# p2.net
KiCad netlist of a schematic drawn in Altium Designer
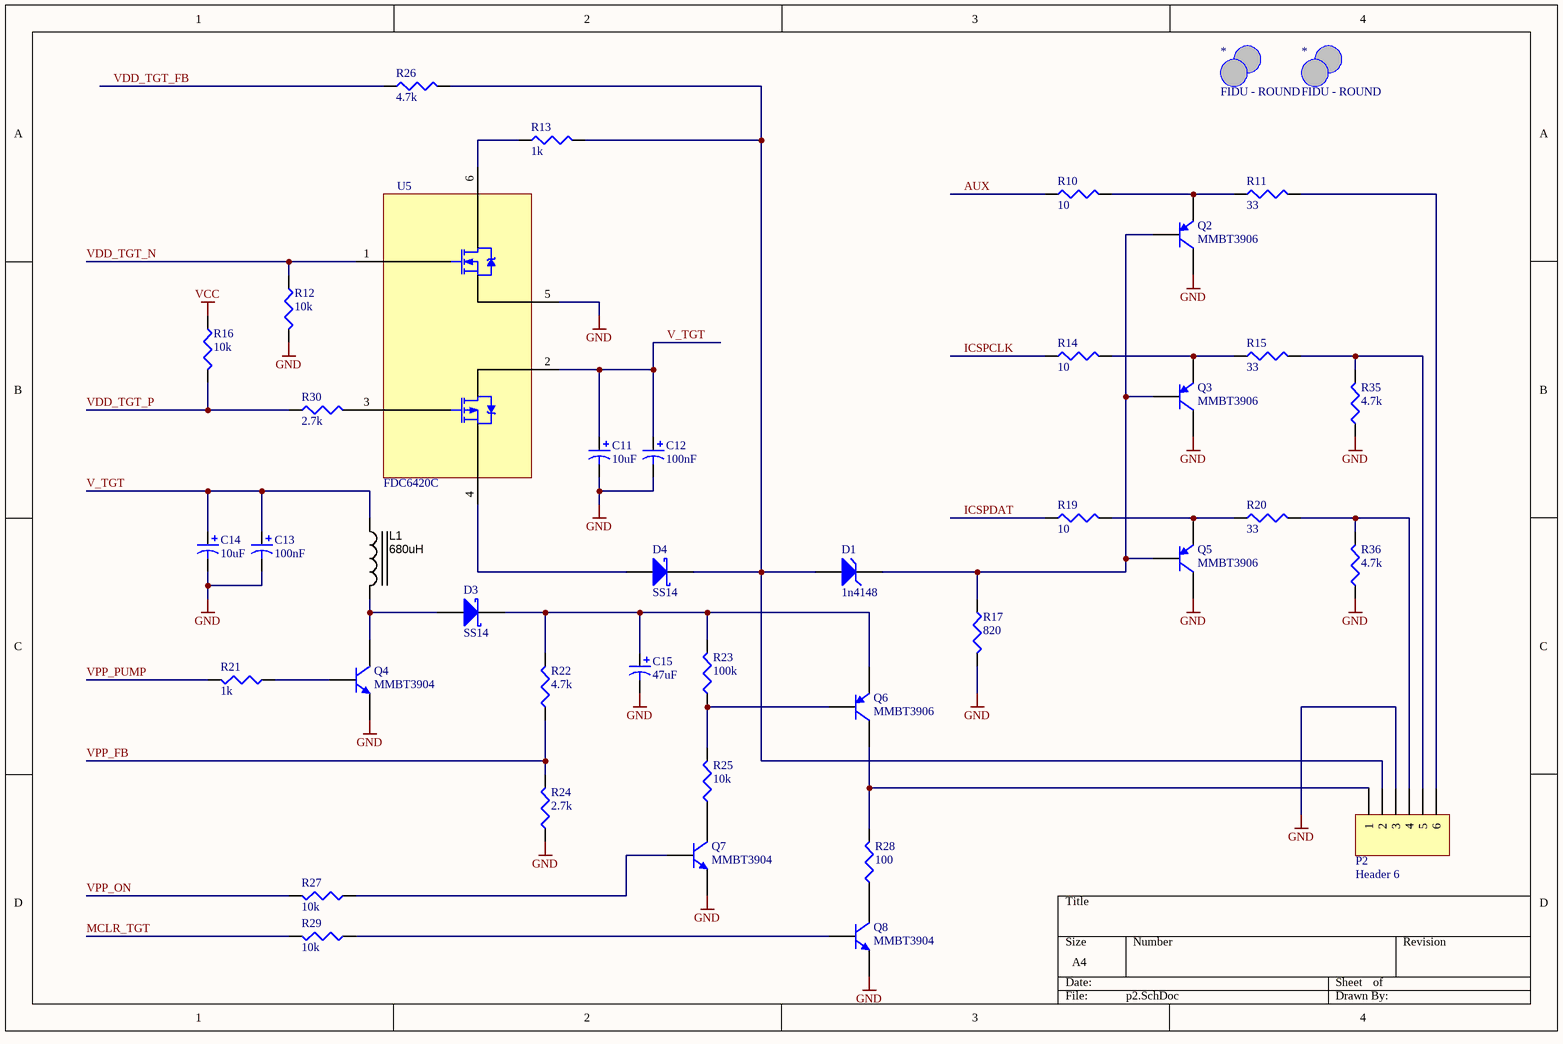
[diagram p0: p2.SchDoc]

(export (version "E")
  (design (tool "Eeschema 10.0.6"))
  (components
    (comp (ref "C11")
      (value "10uF")
      (footprint "C0805")
      (description "Polarized Capacitor (Surface Mount)")
      (fields (field (name "Comment") "Cap Pol3") (field (name "PUBLISHER") "Altium Limited"))
      (libsource (lib "Miscellaneous Devices") (part "Cap Pol3"))
    )
    (comp (ref "C12")
      (value "100nF")
      (footprint "C0805")
      (description "Polarized Capacitor (Surface Mount)")
      (fields (field (name "Comment") "Cap Pol3") (field (name "PUBLISHER") "Altium Limited"))
      (libsource (lib "Miscellaneous Devices") (part "Cap Pol3"))
    )
    (comp (ref "C13")
      (value "100nF")
      (footprint "C0805")
      (description "Polarized Capacitor (Surface Mount)")
      (fields (field (name "Comment") "Cap Pol3") (field (name "PUBLISHER") "Altium Limited"))
      (libsource (lib "Miscellaneous Devices") (part "Cap Pol3"))
    )
    (comp (ref "C14")
      (value "10uF")
      (footprint "C0805")
      (description "Polarized Capacitor (Surface Mount)")
      (fields (field (name "Comment") "Cap Pol3") (field (name "PUBLISHER") "Altium Limited"))
      (libsource (lib "Miscellaneous Devices") (part "Cap Pol3"))
    )
    (comp (ref "C15")
      (value "47uF")
      (footprint "C0805")
      (description "Polarized Capacitor (Surface Mount)")
      (fields (field (name "Comment") "Cap Pol3") (field (name "PUBLISHER") "Altium Limited"))
      (libsource (lib "Miscellaneous Devices") (part "Cap Pol3"))
    )
    (comp (ref "D1")
      (value "1n4148")
      (footprint "SOD-123")
      (description "Surface Mount Zener Diode")
      (fields (field (name "PUBLISHER") "Altium Limited"))
      (libsource (lib "Vishay Lite-On Discrete Diode") (part "BZT52C47"))
    )
    (comp (ref "D3")
      (value "SS14")
      (footprint "SMA")
      (description "Schottky Rectifier")
      (fields (field (name "PUBLISHER") "Altium Limited"))
      (libsource (lib "IR Rectifier - Schottky") (part "10MQ060N"))
    )
    (comp (ref "D4")
      (value "SS14")
      (footprint "SMA")
      (description "Schottky Rectifier")
      (fields (field (name "PUBLISHER") "Altium Limited"))
      (libsource (lib "IR Rectifier - Schottky") (part "10MQ060N"))
    )
    (comp (ref "L1")
      (value "680uH")
      (footprint "IND_WW_DR73")
      (description "Inductor Power 10µH 2.1A 7.6x7.6mm SMD")
      (fields (field (name "TOLERANCE") "±20%"))
      (libsource (lib "PBL - Inductors") (part "INDC_10u_DR73-100-R"))
    )
    (comp (ref "P2")
      (value "Header 6")
      (footprint "HDR1X6")
      (description "Header, 6-Pin")
      (fields (field (name "PUBLISHER") "Altium Limited"))
      (libsource (lib "Miscellaneous Connectors") (part "Header 6"))
    )
    (comp (ref "Q2")
      (value "MMBT3906")
      (footprint "SOT23_N")
      (description "PNP Switching Transistor")
      (fields (field (name "PUBLISHER") "Altium Limited"))
      (libsource (lib "Philips Discrete BJT - Low Power") (part "MMBT3906"))
    )
    (comp (ref "Q3")
      (value "MMBT3906")
      (footprint "SOT23_N")
      (description "PNP Switching Transistor")
      (fields (field (name "PUBLISHER") "Altium Limited"))
      (libsource (lib "Philips Discrete BJT - Low Power") (part "MMBT3906"))
    )
    (comp (ref "Q4")
      (value "MMBT3904")
      (footprint "SOT23_N")
      (description "NPN Switching Transistor")
      (fields (field (name "PUBLISHER") "Altium Limited"))
      (libsource (lib "Philips Discrete BJT - Low Power") (part "MMBT3904"))
    )
    (comp (ref "Q5")
      (value "MMBT3906")
      (footprint "SOT23_N")
      (description "PNP Switching Transistor")
      (fields (field (name "PUBLISHER") "Altium Limited"))
      (libsource (lib "Philips Discrete BJT - Low Power") (part "MMBT3906"))
    )
    (comp (ref "Q6")
      (value "MMBT3906")
      (footprint "SOT23_N")
      (description "PNP Switching Transistor")
      (fields (field (name "PUBLISHER") "Altium Limited"))
      (libsource (lib "Philips Discrete BJT - Low Power") (part "MMBT3906"))
    )
    (comp (ref "Q7")
      (value "MMBT3904")
      (footprint "SOT23_N")
      (description "NPN Switching Transistor")
      (fields (field (name "PUBLISHER") "Altium Limited"))
      (libsource (lib "Philips Discrete BJT - Low Power") (part "MMBT3904"))
    )
    (comp (ref "Q8")
      (value "MMBT3904")
      (footprint "SOT23_N")
      (description "NPN Switching Transistor")
      (fields (field (name "PUBLISHER") "Altium Limited"))
      (libsource (lib "Philips Discrete BJT - Low Power") (part "MMBT3904"))
    )
    (comp (ref "R10")
      (value "10")
      (footprint "RESC2012X70N")
      (description "Resistor")
      (fields (field (name "Comment") "Res3") (field (name "PUBLISHER") "Altium Limited"))
      (libsource (lib "Miscellaneous Devices") (part "Res3"))
    )
    (comp (ref "R11")
      (value "33")
      (footprint "RESC2012X70N")
      (description "Resistor")
      (fields (field (name "Comment") "Res3") (field (name "PUBLISHER") "Altium Limited"))
      (libsource (lib "Miscellaneous Devices") (part "Res3"))
    )
    (comp (ref "R12")
      (value "10k")
      (footprint "RESC2012X70N")
      (description "Resistor")
      (fields (field (name "Comment") "Res3") (field (name "PUBLISHER") "Altium Limited"))
      (libsource (lib "Miscellaneous Devices") (part "Res3"))
    )
    (comp (ref "R13")
      (value "1k")
      (footprint "RESC2012X70N")
      (description "Resistor")
      (fields (field (name "Comment") "Res3") (field (name "PUBLISHER") "Altium Limited"))
      (libsource (lib "Miscellaneous Devices") (part "Res3"))
    )
    (comp (ref "R14")
      (value "10")
      (footprint "RESC2012X70N")
      (description "Resistor")
      (fields (field (name "Comment") "Res3") (field (name "PUBLISHER") "Altium Limited"))
      (libsource (lib "Miscellaneous Devices") (part "Res3"))
    )
    (comp (ref "R15")
      (value "33")
      (footprint "RESC2012X70N")
      (description "Resistor")
      (fields (field (name "Comment") "Res3") (field (name "PUBLISHER") "Altium Limited"))
      (libsource (lib "Miscellaneous Devices") (part "Res3"))
    )
    (comp (ref "R16")
      (value "10k")
      (footprint "RESC2012X70N")
      (description "Resistor")
      (fields (field (name "Comment") "Res3") (field (name "PUBLISHER") "Altium Limited"))
      (libsource (lib "Miscellaneous Devices") (part "Res3"))
    )
    (comp (ref "R17")
      (value "820")
      (footprint "RESC2012X70N")
      (description "Resistor")
      (fields (field (name "Comment") "Res3") (field (name "PUBLISHER") "Altium Limited"))
      (libsource (lib "Miscellaneous Devices") (part "Res3"))
    )
    (comp (ref "R19")
      (value "10")
      (footprint "RESC2012X70N")
      (description "Resistor")
      (fields (field (name "Comment") "Res3") (field (name "PUBLISHER") "Altium Limited"))
      (libsource (lib "Miscellaneous Devices") (part "Res3"))
    )
    (comp (ref "R20")
      (value "33")
      (footprint "RESC2012X70N")
      (description "Resistor")
      (fields (field (name "Comment") "Res3") (field (name "PUBLISHER") "Altium Limited"))
      (libsource (lib "Miscellaneous Devices") (part "Res3"))
    )
    (comp (ref "R21")
      (value "1k")
      (footprint "RESC2012X70N")
      (description "Resistor")
      (fields (field (name "Comment") "Res3") (field (name "PUBLISHER") "Altium Limited"))
      (libsource (lib "Miscellaneous Devices") (part "Res3"))
    )
    (comp (ref "R22")
      (value "4.7k")
      (footprint "RESC2012X70N")
      (description "Resistor")
      (fields (field (name "Comment") "Res3") (field (name "PUBLISHER") "Altium Limited"))
      (libsource (lib "Miscellaneous Devices") (part "Res3"))
    )
    (comp (ref "R23")
      (value "100k")
      (footprint "RESC2012X70N")
      (description "Resistor")
      (fields (field (name "Comment") "Res3") (field (name "PUBLISHER") "Altium Limited"))
      (libsource (lib "Miscellaneous Devices") (part "Res3"))
    )
    (comp (ref "R24")
      (value "2.7k")
      (footprint "RESC2012X70N")
      (description "Resistor")
      (fields (field (name "Comment") "Res3") (field (name "PUBLISHER") "Altium Limited"))
      (libsource (lib "Miscellaneous Devices") (part "Res3"))
    )
    (comp (ref "R25")
      (value "10k")
      (footprint "RESC2012X70N")
      (description "Resistor")
      (fields (field (name "Comment") "Res3") (field (name "PUBLISHER") "Altium Limited"))
      (libsource (lib "Miscellaneous Devices") (part "Res3"))
    )
    (comp (ref "R26")
      (value "4.7k")
      (footprint "RESC2012X70N")
      (description "Resistor")
      (fields (field (name "Comment") "Res3") (field (name "PUBLISHER") "Altium Limited"))
      (libsource (lib "Miscellaneous Devices") (part "Res3"))
    )
    (comp (ref "R27")
      (value "10k")
      (footprint "RESC2012X70N")
      (description "Resistor")
      (fields (field (name "Comment") "Res3") (field (name "PUBLISHER") "Altium Limited"))
      (libsource (lib "Miscellaneous Devices") (part "Res3"))
    )
    (comp (ref "R28")
      (value "100")
      (footprint "RESC2012X70N")
      (description "Resistor")
      (fields (field (name "Comment") "Res3") (field (name "PUBLISHER") "Altium Limited"))
      (libsource (lib "Miscellaneous Devices") (part "Res3"))
    )
    (comp (ref "R29")
      (value "10k")
      (footprint "RESC2012X70N")
      (description "Resistor")
      (fields (field (name "Comment") "Res3") (field (name "PUBLISHER") "Altium Limited"))
      (libsource (lib "Miscellaneous Devices") (part "Res3"))
    )
    (comp (ref "R30")
      (value "2.7k")
      (footprint "RESC2012X70N")
      (description "Resistor")
      (fields (field (name "Comment") "Res3") (field (name "PUBLISHER") "Altium Limited"))
      (libsource (lib "Miscellaneous Devices") (part "Res3"))
    )
    (comp (ref "R35")
      (value "4.7k")
      (footprint "RESC2012X70N")
      (description "Resistor")
      (fields (field (name "Comment") "Res3") (field (name "PUBLISHER") "Altium Limited"))
      (libsource (lib "Miscellaneous Devices") (part "Res3"))
    )
    (comp (ref "R36")
      (value "4.7k")
      (footprint "RESC2012X70N")
      (description "Resistor")
      (fields (field (name "Comment") "Res3") (field (name "PUBLISHER") "Altium Limited"))
      (libsource (lib "Miscellaneous Devices") (part "Res3"))
    )
    (comp (ref "U5") (value "FDC6420C") (footprint "SSOT23") (libsource (lib "pickit") (part "FDC6420C")))
  )
  (nets
    (net (code "1") (name "/AUX") (class "Default")
      (node (ref "R10") (pin "1") (pinfunction "1_1") (pintype "passive"))
    )
    (net (code "2") (name "/ICSPCLK") (class "Default")
      (node (ref "R14") (pin "1") (pinfunction "1_1") (pintype "passive"))
    )
    (net (code "3") (name "/ICSPDAT") (class "Default")
      (node (ref "R19") (pin "1") (pinfunction "1_1") (pintype "passive"))
    )
    (net (code "4") (name "/MCLR_TGT") (class "Default")
      (node (ref "R29") (pin "2") (pinfunction "2_2") (pintype "passive"))
    )
    (net (code "5") (name "/VDD_TGT_FB") (class "Default")
      (node (ref "R26") (pin "1") (pinfunction "1_1") (pintype "passive"))
    )
    (net (code "6") (name "/VDD_TGT_N") (class "Default")
      (node (ref "R12") (pin "1") (pinfunction "1_1") (pintype "passive"))
      (node (ref "U5") (pin "1") (pinfunction "NG_1") (pintype "passive"))
    )
    (net (code "7") (name "/VDD_TGT_P") (class "Default")
      (node (ref "R16") (pin "2") (pinfunction "2_2") (pintype "passive"))
      (node (ref "R30") (pin "1") (pinfunction "1_1") (pintype "passive"))
    )
    (net (code "8") (name "/VPP_FB") (class "Default")
      (node (ref "R22") (pin "1") (pinfunction "1_1") (pintype "passive"))
      (node (ref "R24") (pin "2") (pinfunction "2_2") (pintype "passive"))
    )
    (net (code "9") (name "/VPP_ON") (class "Default")
      (node (ref "R27") (pin "2") (pinfunction "2_2") (pintype "passive"))
    )
    (net (code "10") (name "/VPP_PUMP") (class "Default")
      (node (ref "R21") (pin "2") (pinfunction "2_2") (pintype "passive"))
    )
    (net (code "11") (name "/V_TGT") (class "Default")
      (node (ref "C11") (pin "1") (pinfunction "1_1") (pintype "passive"))
      (node (ref "C12") (pin "1") (pinfunction "1_1") (pintype "passive"))
      (node (ref "C13") (pin "1") (pinfunction "1_1") (pintype "passive"))
      (node (ref "C14") (pin "1") (pinfunction "1_1") (pintype "passive"))
      (node (ref "L1") (pin "1") (pinfunction "1_1") (pintype "passive"))
      (node (ref "U5") (pin "2") (pinfunction "PD_2") (pintype "passive"))
    )
    (net (code "12") (name "GND") (class "Default")
      (node (ref "C11") (pin "2") (pinfunction "2_2") (pintype "passive"))
      (node (ref "C12") (pin "2") (pinfunction "2_2") (pintype "passive"))
      (node (ref "C13") (pin "2") (pinfunction "2_2") (pintype "passive"))
      (node (ref "C14") (pin "2") (pinfunction "2_2") (pintype "passive"))
      (node (ref "C15") (pin "2") (pinfunction "2_2") (pintype "passive"))
      (node (ref "P2") (pin "3") (pinfunction "3_3") (pintype "passive"))
      (node (ref "Q2") (pin "3") (pinfunction "C_3") (pintype "passive"))
      (node (ref "Q3") (pin "3") (pinfunction "C_3") (pintype "passive"))
      (node (ref "Q4") (pin "2") (pinfunction "E_2") (pintype "passive"))
      (node (ref "Q5") (pin "3") (pinfunction "C_3") (pintype "passive"))
      (node (ref "Q7") (pin "2") (pinfunction "E_2") (pintype "passive"))
      (node (ref "Q8") (pin "2") (pinfunction "E_2") (pintype "passive"))
      (node (ref "R12") (pin "2") (pinfunction "2_2") (pintype "passive"))
      (node (ref "R17") (pin "2") (pinfunction "2_2") (pintype "passive"))
      (node (ref "R24") (pin "1") (pinfunction "1_1") (pintype "passive"))
      (node (ref "R35") (pin "1") (pinfunction "1_1") (pintype "passive"))
      (node (ref "R36") (pin "1") (pinfunction "1_1") (pintype "passive"))
      (node (ref "U5") (pin "5") (pinfunction "NS_5") (pintype "passive"))
    )
    (net (code "13") (name "Net-(D1-A)") (class "Default")
      (node (ref "D1") (pin "1") (pinfunction "A_1") (pintype "passive"))
      (node (ref "D4") (pin "2") (pinfunction "K_2") (pintype "passive"))
      (node (ref "P2") (pin "2") (pinfunction "2_2") (pintype "passive"))
      (node (ref "R13") (pin "2") (pinfunction "2_2") (pintype "passive"))
      (node (ref "R26") (pin "2") (pinfunction "2_2") (pintype "passive"))
    )
    (net (code "14") (name "Net-(D1-K)") (class "Default")
      (node (ref "D1") (pin "2") (pinfunction "K_2") (pintype "passive"))
      (node (ref "Q2") (pin "1") (pinfunction "B_1") (pintype "passive"))
      (node (ref "Q3") (pin "1") (pinfunction "B_1") (pintype "passive"))
      (node (ref "Q5") (pin "1") (pinfunction "B_1") (pintype "passive"))
      (node (ref "R17") (pin "1") (pinfunction "1_1") (pintype "passive"))
    )
    (net (code "15") (name "Net-(D3-A)") (class "Default")
      (node (ref "D3") (pin "1") (pinfunction "A_1") (pintype "passive"))
      (node (ref "L1") (pin "2") (pinfunction "2_2") (pintype "passive"))
      (node (ref "Q4") (pin "3") (pinfunction "C_3") (pintype "passive"))
    )
    (net (code "16") (name "Net-(D3-K)") (class "Default")
      (node (ref "C15") (pin "1") (pinfunction "1_1") (pintype "passive"))
      (node (ref "D3") (pin "2") (pinfunction "K_2") (pintype "passive"))
      (node (ref "Q6") (pin "2") (pinfunction "E_2") (pintype "passive"))
      (node (ref "R22") (pin "2") (pinfunction "2_2") (pintype "passive"))
      (node (ref "R23") (pin "2") (pinfunction "2_2") (pintype "passive"))
    )
    (net (code "17") (name "Net-(D4-A)") (class "Default")
      (node (ref "D4") (pin "1") (pinfunction "A_1") (pintype "passive"))
      (node (ref "U5") (pin "4") (pinfunction "PS_4") (pintype "passive"))
    )
    (net (code "18") (name "Net-(P2-Pad4)") (class "Default")
      (node (ref "P2") (pin "4") (pinfunction "4_4") (pintype "passive"))
      (node (ref "R20") (pin "2") (pinfunction "2_2") (pintype "passive"))
      (node (ref "R36") (pin "2") (pinfunction "2_2") (pintype "passive"))
    )
    (net (code "19") (name "Net-(P2-Pad5)") (class "Default")
      (node (ref "P2") (pin "5") (pinfunction "5_5") (pintype "passive"))
      (node (ref "R15") (pin "2") (pinfunction "2_2") (pintype "passive"))
      (node (ref "R35") (pin "2") (pinfunction "2_2") (pintype "passive"))
    )
    (net (code "20") (name "Net-(P2-Pad6)") (class "Default")
      (node (ref "P2") (pin "6") (pinfunction "6_6") (pintype "passive"))
      (node (ref "R11") (pin "2") (pinfunction "2_2") (pintype "passive"))
    )
    (net (code "21") (name "Net-(Q2-E)") (class "Default")
      (node (ref "Q2") (pin "2") (pinfunction "E_2") (pintype "passive"))
      (node (ref "R10") (pin "2") (pinfunction "2_2") (pintype "passive"))
      (node (ref "R11") (pin "1") (pinfunction "1_1") (pintype "passive"))
    )
    (net (code "22") (name "Net-(Q3-E)") (class "Default")
      (node (ref "Q3") (pin "2") (pinfunction "E_2") (pintype "passive"))
      (node (ref "R14") (pin "2") (pinfunction "2_2") (pintype "passive"))
      (node (ref "R15") (pin "1") (pinfunction "1_1") (pintype "passive"))
    )
    (net (code "23") (name "Net-(Q4-B)") (class "Default")
      (node (ref "Q4") (pin "1") (pinfunction "B_1") (pintype "passive"))
      (node (ref "R21") (pin "1") (pinfunction "1_1") (pintype "passive"))
    )
    (net (code "24") (name "Net-(Q5-E)") (class "Default")
      (node (ref "Q5") (pin "2") (pinfunction "E_2") (pintype "passive"))
      (node (ref "R19") (pin "2") (pinfunction "2_2") (pintype "passive"))
      (node (ref "R20") (pin "1") (pinfunction "1_1") (pintype "passive"))
    )
    (net (code "25") (name "Net-(Q6-B)") (class "Default")
      (node (ref "Q6") (pin "1") (pinfunction "B_1") (pintype "passive"))
      (node (ref "R23") (pin "1") (pinfunction "1_1") (pintype "passive"))
      (node (ref "R25") (pin "2") (pinfunction "2_2") (pintype "passive"))
    )
    (net (code "26") (name "Net-(Q6-C)") (class "Default")
      (node (ref "P2") (pin "1") (pinfunction "1_1") (pintype "passive"))
      (node (ref "Q6") (pin "3") (pinfunction "C_3") (pintype "passive"))
      (node (ref "R28") (pin "2") (pinfunction "2_2") (pintype "passive"))
    )
    (net (code "27") (name "Net-(Q7-B)") (class "Default")
      (node (ref "Q7") (pin "1") (pinfunction "B_1") (pintype "passive"))
      (node (ref "R27") (pin "1") (pinfunction "1_1") (pintype "passive"))
    )
    (net (code "28") (name "Net-(Q7-C)") (class "Default")
      (node (ref "Q7") (pin "3") (pinfunction "C_3") (pintype "passive"))
      (node (ref "R25") (pin "1") (pinfunction "1_1") (pintype "passive"))
    )
    (net (code "29") (name "Net-(Q8-B)") (class "Default")
      (node (ref "Q8") (pin "1") (pinfunction "B_1") (pintype "passive"))
      (node (ref "R29") (pin "1") (pinfunction "1_1") (pintype "passive"))
    )
    (net (code "30") (name "Net-(Q8-C)") (class "Default")
      (node (ref "Q8") (pin "3") (pinfunction "C_3") (pintype "passive"))
      (node (ref "R28") (pin "1") (pinfunction "1_1") (pintype "passive"))
    )
    (net (code "31") (name "Net-(U5-ND)") (class "Default")
      (node (ref "R13") (pin "1") (pinfunction "1_1") (pintype "passive"))
      (node (ref "U5") (pin "6") (pinfunction "ND_6") (pintype "passive"))
    )
    (net (code "32") (name "Net-(U5-PG)") (class "Default")
      (node (ref "R30") (pin "2") (pinfunction "2_2") (pintype "passive"))
      (node (ref "U5") (pin "3") (pinfunction "PG_3") (pintype "passive"))
    )
    (net (code "33") (name "VCC") (class "Default")
      (node (ref "R16") (pin "1") (pinfunction "1_1") (pintype "passive"))
    )
  )
)
